# powersupply.net
KiCad netlist of a schematic drawn in EAGLE
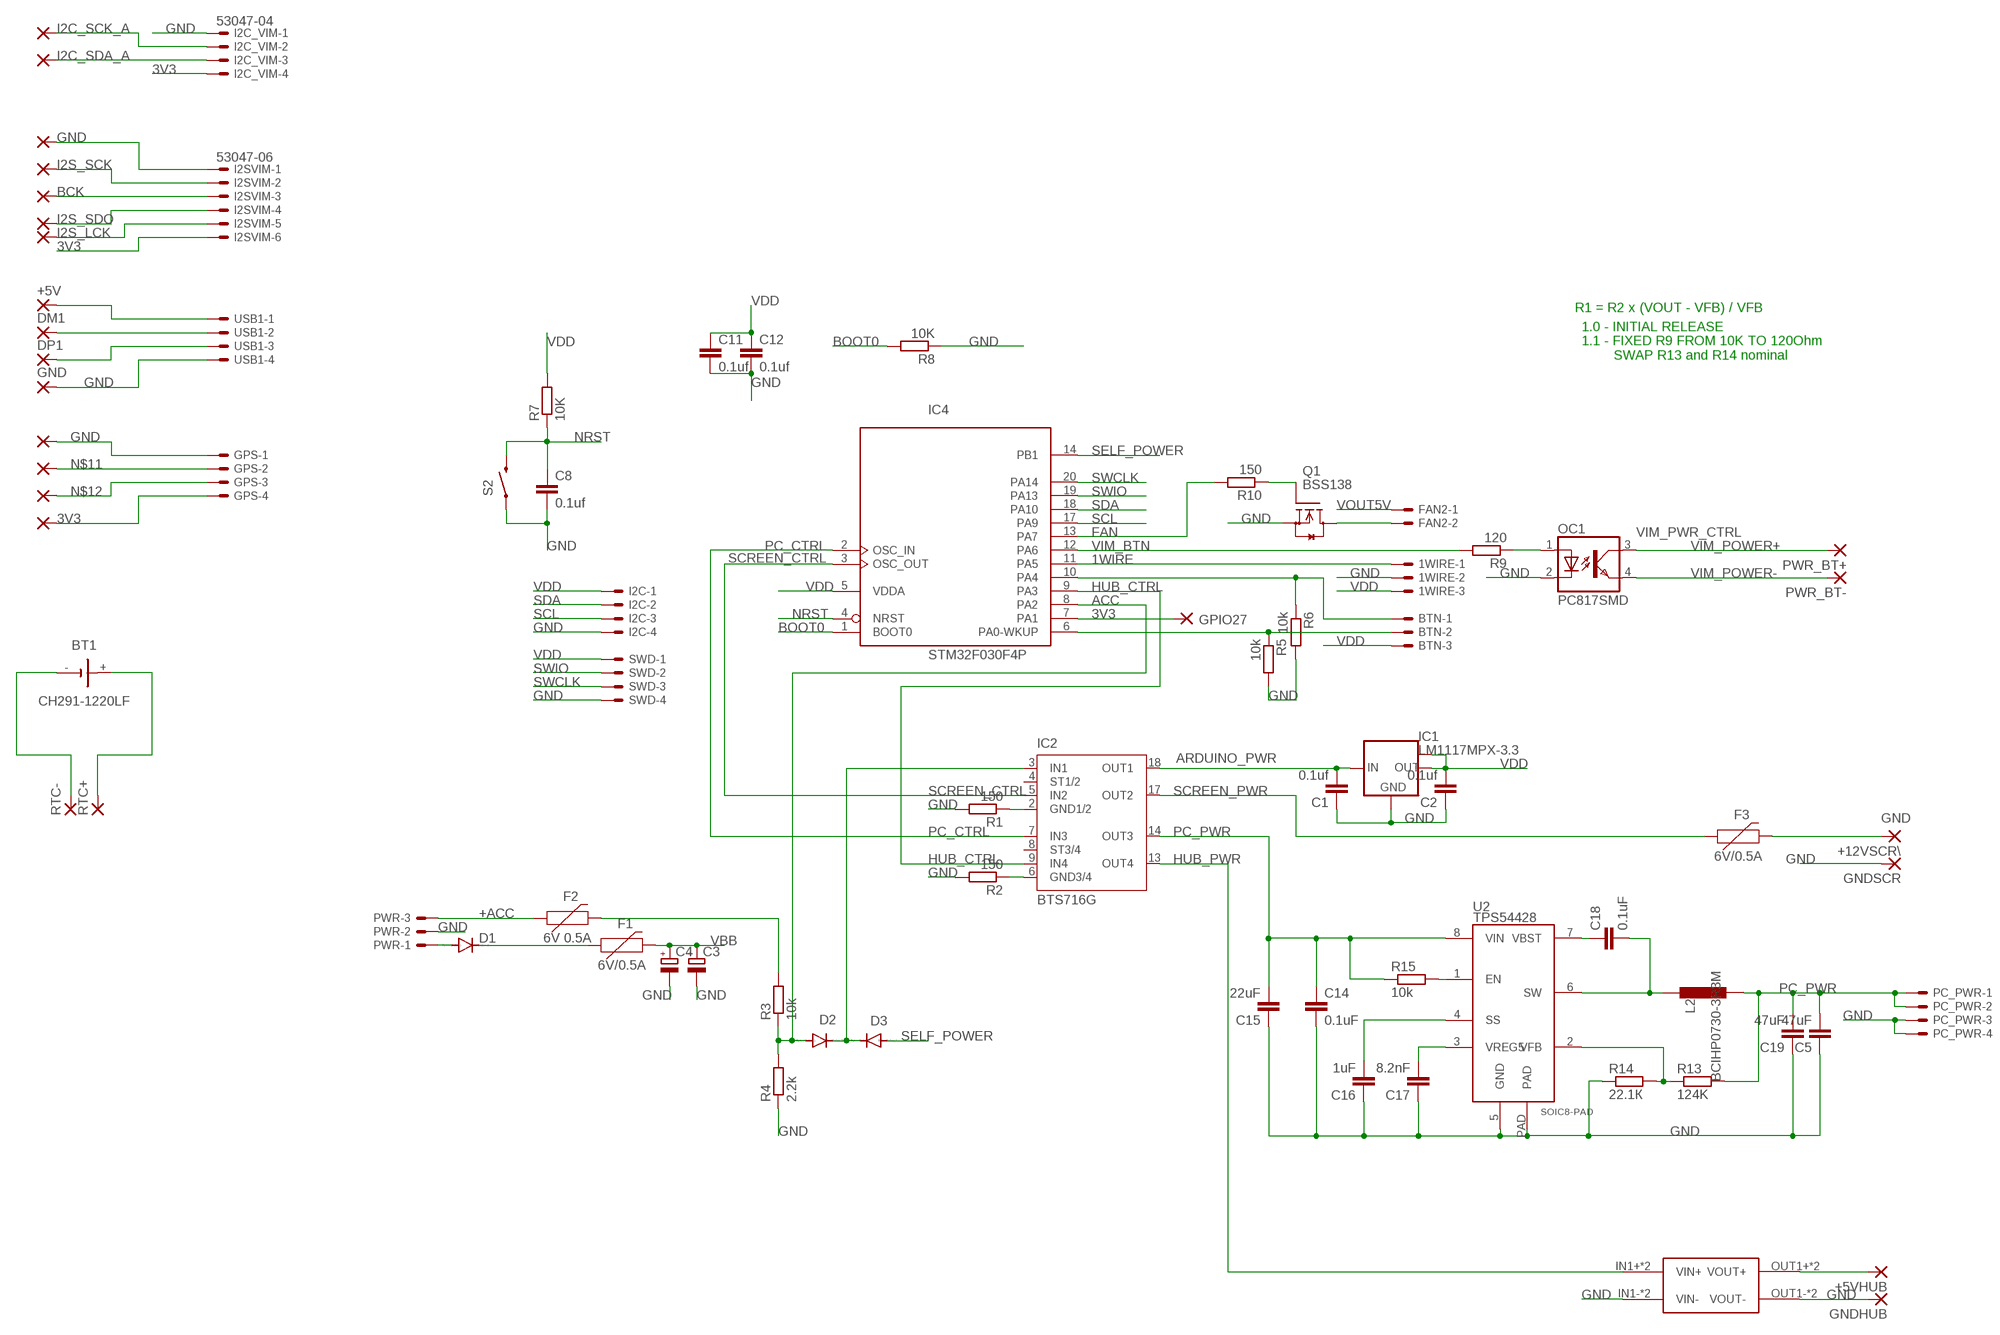
[diagram p0: schematic, sheet 1]

(export (version "E")
  (design (tool "Eeschema 10.0.6"))
  (components
    (comp (ref "+5V")
      (value "1,6/0,8")
      (footprint "eagle-import:1,6_0,8")
      (libsource (lib "eagle-import") (part "1,6/0,8"))
    )
    (comp (ref "+5VHUB")
      (value "1,6/0,8")
      (footprint "eagle-import:1,6_0,8")
      (libsource (lib "eagle-import") (part "1,6/0,8"))
    )
    (comp (ref "+12VSCR\\")
      (value "1,6/0,8")
      (footprint "eagle-import:1,6_0,8")
      (libsource (lib "eagle-import") (part "1,6/0,8"))
    )
    (comp (ref "1WIRE")
      (value "53047-03")
      (footprint "eagle-import:53047-03")
      (fields (field (name "MF") "MOLEX") (field (name "MPN") "530470310"))
      (libsource (lib "eagle-import") (part "53?-03047"))
    )
    (comp (ref "3V3_1")
      (value "1,6/0,8")
      (footprint "eagle-import:1,6_0,8")
      (libsource (lib "eagle-import") (part "1,6/0,8"))
    )
    (comp (ref "22")
      (value "1,6/0,8")
      (footprint "eagle-import:1,6_0,8")
      (libsource (lib "eagle-import") (part "1,6/0,8"))
    )
    (comp (ref "23")
      (value "1,6/0,8")
      (footprint "eagle-import:1,6_0,8")
      (libsource (lib "eagle-import") (part "1,6/0,8"))
    )
    (comp (ref "28")
      (value "1,6/0,8")
      (footprint "eagle-import:1,6_0,8")
      (libsource (lib "eagle-import") (part "1,6/0,8"))
    )
    (comp (ref "29")
      (value "1,6/0,8")
      (footprint "eagle-import:1,6_0,8")
      (libsource (lib "eagle-import") (part "1,6/0,8"))
    )
    (comp (ref "30")
      (value "1,6/0,8")
      (footprint "eagle-import:1,6_0,8")
      (libsource (lib "eagle-import") (part "1,6/0,8"))
    )
    (comp (ref "31")
      (value "1,6/0,8")
      (footprint "eagle-import:1,6_0,8")
      (libsource (lib "eagle-import") (part "1,6/0,8"))
    )
    (comp (ref "32")
      (value "1,6/0,8")
      (footprint "eagle-import:1,6_0,8")
      (libsource (lib "eagle-import") (part "1,6/0,8"))
    )
    (comp (ref "BT1")
      (value "CH291-1220LF")
      (footprint "eagle-import:CH291-1220LF")
      (libsource (lib "eagle-import") (part "CH291-1220LF"))
    )
    (comp (ref "BTN")
      (value "53047-03")
      (footprint "eagle-import:53047-03")
      (fields (field (name "MF") "MOLEX") (field (name "MPN") "530470310"))
      (libsource (lib "eagle-import") (part "53?-03047"))
    )
    (comp (ref "C1")
      (value "0.1uf")
      (footprint "eagle-import:C0805")
      (fields (field (name "MPN") "CL21B104KBFNNNE"))
      (libsource (lib "eagle-import") (part "C-EUC0805"))
    )
    (comp (ref "C2")
      (value "0.1uf")
      (footprint "eagle-import:C0805")
      (fields (field (name "MPN") "CL21B104KBFNNNE"))
      (libsource (lib "eagle-import") (part "C-EUC0805"))
    )
    (comp (ref "C3")
      (value "CPOL-EUUD-8X10")
      (footprint "eagle-import:UD-8X10_NICHICON")
      (libsource (lib "eagle-import") (part "CPOL-EUUD-8X10"))
    )
    (comp (ref "C4")
      (value "CPOL-EUUD-8X10")
      (footprint "eagle-import:UD-8X10_NICHICON")
      (libsource (lib "eagle-import") (part "CPOL-EUUD-8X10"))
    )
    (comp (ref "C5")
      (value "47uF")
      (footprint "eagle-import:C1206")
      (fields (field (name "MPN") "CL31A476MPHNNNE"))
      (libsource (lib "eagle-import") (part "C-EUC1206"))
    )
    (comp (ref "C8")
      (value "0.1uf")
      (footprint "eagle-import:C0805")
      (fields (field (name "MPN") "CL21B104KBFNNNE"))
      (libsource (lib "eagle-import") (part "C-EUC0805"))
    )
    (comp (ref "C11")
      (value "0.1uf")
      (footprint "eagle-import:C0805")
      (fields (field (name "MPN") "CL21B104KBFNNNE"))
      (libsource (lib "eagle-import") (part "C-EUC0805"))
    )
    (comp (ref "C12")
      (value "0.1uf")
      (footprint "eagle-import:C0805")
      (fields (field (name "MPN") "CL21B104KBFNNNE"))
      (libsource (lib "eagle-import") (part "C-EUC0805"))
    )
    (comp (ref "C14")
      (value "0.1uF")
      (footprint "eagle-import:C0805K")
      (fields (field (name "MPN") "CL21B104KBFNNNE"))
      (libsource (lib "eagle-import") (part "C-EUC0805K"))
    )
    (comp (ref "C15")
      (value "22uF")
      (footprint "eagle-import:C0805")
      (fields (field (name "MPN") "CL31A226KAHNNNE"))
      (libsource (lib "eagle-import") (part "C-EUC0805"))
    )
    (comp (ref "C16")
      (value "1uF")
      (footprint "eagle-import:C0805K")
      (fields (field (name "MPN") "CL21B105KAFNNNE"))
      (libsource (lib "eagle-import") (part "C-EUC0805K"))
    )
    (comp (ref "C17")
      (value "8.2nF")
      (footprint "eagle-import:C0805K")
      (fields (field (name "MPN") "CL21B822KBANNNC"))
      (libsource (lib "eagle-import") (part "C-EUC0805K"))
    )
    (comp (ref "C18")
      (value "0.1uF")
      (footprint "eagle-import:C0805K")
      (fields (field (name "MPN") "CL21B104KBFNNNE"))
      (libsource (lib "eagle-import") (part "C-EUC0805K"))
    )
    (comp (ref "C19")
      (value "47uF")
      (footprint "eagle-import:C1206")
      (fields (field (name "MPN") "CL31A476MPHNNNE"))
      (libsource (lib "eagle-import") (part "C-EUC1206"))
    )
    (comp (ref "D1")
      (value "DIODE-SMB")
      (footprint "eagle-import:SMB")
      (libsource (lib "eagle-import") (part "DIODE-SMB"))
    )
    (comp (ref "D2")
      (value "DIODE-SOD323-W")
      (footprint "eagle-import:SOD323-W")
      (libsource (lib "eagle-import") (part "DIODE-SOD323-W"))
    )
    (comp (ref "D3")
      (value "DIODE-SOD323-W")
      (footprint "eagle-import:SOD323-W")
      (libsource (lib "eagle-import") (part "DIODE-SOD323-W"))
    )
    (comp (ref "DM1")
      (value "1,6/0,8")
      (footprint "eagle-import:1,6_0,8")
      (libsource (lib "eagle-import") (part "1,6/0,8"))
    )
    (comp (ref "DP1")
      (value "1,6/0,8")
      (footprint "eagle-import:1,6_0,8")
      (libsource (lib "eagle-import") (part "1,6/0,8"))
    )
    (comp (ref "F1")
      (value "6V/0.5A")
      (footprint "eagle-import:1206")
      (libsource (lib "eagle-import") (part "PPTC_HALF-AMP"))
    )
    (comp (ref "F2")
      (value "6V 0.5A")
      (footprint "eagle-import:0805")
      (libsource (lib "eagle-import") (part "PPTC_6V500MA"))
    )
    (comp (ref "F3")
      (value "6V/0.5A")
      (footprint "eagle-import:1206")
      (libsource (lib "eagle-import") (part "PPTC_HALF-AMP"))
    )
    (comp (ref "FAN2")
      (value "53047-02")
      (footprint "eagle-import:53047-02")
      (fields (field (name "MF") "MOLEX") (field (name "MPN") "53047-0210"))
      (libsource (lib "eagle-import") (part "53?-02047"))
    )
    (comp (ref "GND")
      (value "1,6/0,8")
      (footprint "eagle-import:1,6_0,8")
      (libsource (lib "eagle-import") (part "1,6/0,8"))
    )
    (comp (ref "GNDGPS")
      (value "1,6/0,8")
      (footprint "eagle-import:1,6_0,8")
      (libsource (lib "eagle-import") (part "1,6/0,8"))
    )
    (comp (ref "GNDHUB")
      (value "1,6/0,8")
      (footprint "eagle-import:1,6_0,8")
      (libsource (lib "eagle-import") (part "1,6/0,8"))
    )
    (comp (ref "GNDSCR")
      (value "1,6/0,8")
      (footprint "eagle-import:1,6_0,8")
      (libsource (lib "eagle-import") (part "1,6/0,8"))
    )
    (comp (ref "GPIO27")
      (value "1,6/0,8")
      (footprint "eagle-import:1,6_0,8")
      (libsource (lib "eagle-import") (part "1,6/0,8"))
    )
    (comp (ref "GPS")
      (value "53047-04")
      (footprint "eagle-import:53047-04")
      (fields (field (name "MF") "WALDOM/MOLEX") (field (name "MPN") "53047-0410"))
      (libsource (lib "eagle-import") (part "53?-04047"))
    )
    (comp (ref "I2C")
      (value "i2c")
      (footprint "eagle-import:53047-04")
      (fields (field (name "MF") "WALDOM/MOLEX") (field (name "MPN") "53047-0410"))
      (libsource (lib "eagle-import") (part "53?-04047"))
    )
    (comp (ref "I2C_VIM")
      (value "53047-04")
      (footprint "eagle-import:53047-04")
      (fields (field (name "MF") "WALDOM/MOLEX") (field (name "MPN") "53047-0410"))
      (libsource (lib "eagle-import") (part "53?-04047"))
    )
    (comp (ref "I2SVIM")
      (value "53047-06")
      (footprint "eagle-import:53047-06")
      (libsource (lib "eagle-import") (part "53?-06047"))
    )
    (comp (ref "IC1")
      (value "LM1117MPX-3.3")
      (footprint "eagle-import:SOT223")
      (fields (field (name "MPN") "LM1117IMPX-3.3/NOPB"))
      (libsource (lib "eagle-import") (part "LM1117MPX-3.3"))
    )
    (comp (ref "IC2")
      (value "BTS716G")
      (footprint "eagle-import:PG-DSO-20")
      (libsource (lib "eagle-import") (part "BTS716G"))
    )
    (comp (ref "IC4")
      (value "STM32F030F4P")
      (footprint "eagle-import:TSSOP20-I")
      (libsource (lib "eagle-import") (part "STM32F030FP4"))
    )
    (comp (ref "L2")
      (value "BCIHP0730-3R3M")
      (footprint "eagle-import:VLS4045EX")
      (fields (field (name "MPN") "VLS5045EX-3R3N"))
      (libsource (lib "eagle-import") (part "VLS5045EX"))
    )
    (comp (ref "OC1")
      (value "PC817SMD")
      (footprint "eagle-import:DIL04SMD")
      (fields (field (name "MPN") "PC817X2CSP9F"))
      (libsource (lib "eagle-import") (part "PC817SMD"))
    )
    (comp (ref "PC_PWR")
      (value "i2c")
      (footprint "eagle-import:53047-04")
      (fields (field (name "MF") "WALDOM/MOLEX") (field (name "MPN") "53047-0410"))
      (libsource (lib "eagle-import") (part "53?-04047"))
    )
    (comp (ref "PWR")
      (value "JST-XH-03-PIN-ROUND-PAD")
      (footprint "eagle-import:JST-XH-03-PACKAGE-ROUND-PAD")
      (libsource (lib "eagle-import") (part "JST-XH-03-PIN-ROUND-PAD"))
    )
    (comp (ref "PWR_BT+")
      (value "1,6/0,8")
      (footprint "eagle-import:1,6_0,8")
      (libsource (lib "eagle-import") (part "1,6/0,8"))
    )
    (comp (ref "PWR_BT-")
      (value "1,6/0,8")
      (footprint "eagle-import:1,6_0,8")
      (libsource (lib "eagle-import") (part "1,6/0,8"))
    )
    (comp (ref "Q1")
      (value "BSS138")
      (footprint "eagle-import:SOT23")
      (libsource (lib "eagle-import") (part "BSS138"))
    )
    (comp (ref "R1")
      (value "150")
      (footprint "eagle-import:R0805")
      (libsource (lib "eagle-import") (part "resistor_348_R-EU_R0805"))
    )
    (comp (ref "R2")
      (value "150")
      (footprint "eagle-import:R0805")
      (libsource (lib "eagle-import") (part "resistor_348_R-EU_R0805"))
    )
    (comp (ref "R3")
      (value "10k")
      (footprint "eagle-import:R0805")
      (libsource (lib "eagle-import") (part "resistor_348_R-EU_R0805"))
    )
    (comp (ref "R4")
      (value "2.2k")
      (footprint "eagle-import:R0805")
      (libsource (lib "eagle-import") (part "resistor_348_R-EU_R0805"))
    )
    (comp (ref "R5")
      (value "10k")
      (footprint "eagle-import:R0805")
      (libsource (lib "eagle-import") (part "resistor_348_R-EU_R0805"))
    )
    (comp (ref "R6")
      (value "10k")
      (footprint "eagle-import:R0805")
      (libsource (lib "eagle-import") (part "resistor_348_R-EU_R0805"))
    )
    (comp (ref "R7")
      (value "10K")
      (footprint "eagle-import:M0805")
      (libsource (lib "eagle-import") (part "R-EU_M0805"))
    )
    (comp (ref "R8")
      (value "10K")
      (footprint "eagle-import:M0805")
      (libsource (lib "eagle-import") (part "R-EU_M0805"))
    )
    (comp (ref "R9")
      (value "120")
      (footprint "eagle-import:M0805")
      (libsource (lib "eagle-import") (part "R-EU_M0805"))
    )
    (comp (ref "R10")
      (value "150")
      (footprint "eagle-import:R0805")
      (libsource (lib "eagle-import") (part "resistor_348_R-EU_R0805"))
    )
    (comp (ref "R13")
      (value "124K")
      (footprint "eagle-import:M0805")
      (fields (field (name "MPN") "TR0805B22K1P0525Z"))
      (libsource (lib "eagle-import") (part "R-EU_M0805"))
    )
    (comp (ref "R14")
      (value "22.1К")
      (footprint "eagle-import:M0805")
      (fields (field (name "MPN") "AR05BTCW1253"))
      (libsource (lib "eagle-import") (part "R-EU_M0805"))
    )
    (comp (ref "R15")
      (value "10k")
      (footprint "eagle-import:M0805")
      (libsource (lib "eagle-import") (part "R-EU_M0805"))
    )
    (comp (ref "RTC+")
      (value "1,6/0,8")
      (footprint "eagle-import:1,6_0,8")
      (libsource (lib "eagle-import") (part "1,6/0,8"))
    )
    (comp (ref "RTC-")
      (value "1,6/0,8")
      (footprint "eagle-import:1,6_0,8")
      (libsource (lib "eagle-import") (part "1,6/0,8"))
    )
    (comp (ref "RX")
      (value "1,6/0,8")
      (footprint "eagle-import:1,6_0,8")
      (libsource (lib "eagle-import") (part "1,6/0,8"))
    )
    (comp (ref "S2")
      (value "SWITCH-MOMENTARY-2-SMD-1101NE")
      (footprint "eagle-import:TACTILE-SWITCH-1101NE")
      (libsource (lib "eagle-import") (part "SWITCH-MOMENTARY-2-SMD-1101NE"))
    )
    (comp (ref "SWD")
      (value "53047-04")
      (footprint "eagle-import:53047-04")
      (fields (field (name "MF") "WALDOM/MOLEX") (field (name "MPN") "53047-0410"))
      (libsource (lib "eagle-import") (part "53?-04047"))
    )
    (comp (ref "TX")
      (value "1,6/0,8")
      (footprint "eagle-import:1,6_0,8")
      (libsource (lib "eagle-import") (part "1,6/0,8"))
    )
    (comp (ref "U$1")
      (value "MP1584")
      (footprint "eagle-import:DC-BRICK")
      (libsource (lib "eagle-import") (part "MP1584"))
    )
    (comp (ref "U2")
      (value "TPS54428")
      (footprint "eagle-import:PDSO-8")
      (fields (field (name "PACKAGE") "SOIC8-PAD") (field (name "MPN") "TPS54428DDAR"))
      (libsource (lib "eagle-import") (part "TPS54428"))
    )
    (comp (ref "USB1")
      (value "53047-04")
      (footprint "eagle-import:53047-04")
      (fields (field (name "MF") "WALDOM/MOLEX") (field (name "MPN") "53047-0410"))
      (libsource (lib "eagle-import") (part "53?-04047"))
    )
  )
  (nets
    (net (code "1") (name "/+ACC") (class "Default")
      (node (ref "F2") (pin "2") (pinfunction "2_2") (pintype "bidirectional"))
      (node (ref "R3") (pin "2") (pinfunction "2_2") (pintype "passive"))
    )
    (net (code "2") (name "/1WIRE") (class "Default")
      (node (ref "1WIRE") (pin "1") (pinfunction "S_1") (pintype "passive"))
      (node (ref "IC4") (pin "11") (pinfunction "PA5_11") (pintype "bidirectional"))
    )
    (net (code "3") (name "/3V3") (class "Default")
      (node (ref "3V3_1") (pin "1") (pinfunction "P_1") (pintype "passive"))
      (node (ref "GPIO27") (pin "1") (pinfunction "P_1") (pintype "passive"))
      (node (ref "GPS") (pin "4") (pinfunction "S_4") (pintype "passive"))
      (node (ref "I2C_VIM") (pin "4") (pinfunction "S_4") (pintype "passive"))
      (node (ref "I2SVIM") (pin "6") (pinfunction "S_6") (pintype "passive"))
      (node (ref "IC4") (pin "7") (pinfunction "PA1_7") (pintype "bidirectional"))
    )
    (net (code "4") (name "/ACC") (class "Default")
      (node (ref "D2") (pin "A") (pinfunction "A_A") (pintype "passive"))
      (node (ref "IC4") (pin "8") (pinfunction "PA2_8") (pintype "bidirectional"))
      (node (ref "R3") (pin "1") (pinfunction "1_1") (pintype "passive"))
      (node (ref "R4") (pin "2") (pinfunction "2_2") (pintype "passive"))
    )
    (net (code "5") (name "/ARDUINO_PWR") (class "Default")
      (node (ref "C1") (pin "2") (pinfunction "2_2") (pintype "passive"))
      (node (ref "IC1") (pin "3") (pinfunction "IN_3") (pintype "input"))
      (node (ref "IC2") (pin "18") (pinfunction "OUT1_18") (pintype "output"))
    )
    (net (code "6") (name "/BCK") (class "Default")
      (node (ref "30") (pin "1") (pinfunction "P_1") (pintype "passive"))
      (node (ref "I2SVIM") (pin "3") (pinfunction "S_3") (pintype "passive"))
    )
    (net (code "7") (name "/BOOT0") (class "Default")
      (node (ref "IC4") (pin "1") (pinfunction "BOOT0_1") (pintype "input"))
      (node (ref "R8") (pin "2") (pinfunction "2_2") (pintype "passive"))
    )
    (net (code "8") (name "/FAN") (class "Default")
      (node (ref "IC4") (pin "13") (pinfunction "PA7_13") (pintype "bidirectional"))
      (node (ref "R10") (pin "2") (pinfunction "2_2") (pintype "passive"))
    )
    (net (code "9") (name "/GND") (class "Default")
      (node (ref "1WIRE") (pin "2") (pinfunction "S_2") (pintype "passive"))
      (node (ref "28") (pin "1") (pinfunction "P_1") (pintype "passive"))
      (node (ref "C1") (pin "1") (pinfunction "1_1") (pintype "passive"))
      (node (ref "C11") (pin "2") (pinfunction "2_2") (pintype "passive"))
      (node (ref "C12") (pin "2") (pinfunction "2_2") (pintype "passive"))
      (node (ref "C14") (pin "2") (pinfunction "2_2") (pintype "passive"))
      (node (ref "C15") (pin "1") (pinfunction "1_1") (pintype "passive"))
      (node (ref "C16") (pin "1") (pinfunction "1_1") (pintype "passive"))
      (node (ref "C17") (pin "1") (pinfunction "1_1") (pintype "passive"))
      (node (ref "C19") (pin "1") (pinfunction "1_1") (pintype "passive"))
      (node (ref "C2") (pin "1") (pinfunction "1_1") (pintype "passive"))
      (node (ref "C3") (pin "-") (pinfunction "-_-") (pintype "passive"))
      (node (ref "C4") (pin "-") (pinfunction "-_-") (pintype "passive"))
      (node (ref "C5") (pin "1") (pinfunction "1_1") (pintype "passive"))
      (node (ref "C8") (pin "2") (pinfunction "2_2") (pintype "passive"))
      (node (ref "GND") (pin "1") (pinfunction "P_1") (pintype "passive"))
      (node (ref "GNDGPS") (pin "1") (pinfunction "P_1") (pintype "passive"))
      (node (ref "GNDHUB") (pin "1") (pinfunction "P_1") (pintype "passive"))
      (node (ref "GNDSCR") (pin "1") (pinfunction "P_1") (pintype "passive"))
      (node (ref "GPS") (pin "1") (pinfunction "S_1") (pintype "passive"))
      (node (ref "I2C") (pin "4") (pinfunction "S_4") (pintype "passive"))
      (node (ref "I2C_VIM") (pin "1") (pinfunction "S_1") (pintype "passive"))
      (node (ref "I2SVIM") (pin "1") (pinfunction "S_1") (pintype "passive"))
      (node (ref "IC1") (pin "1") (pinfunction "GND_1") (pintype "input"))
      (node (ref "OC1") (pin "2") (pinfunction "C_2") (pintype "passive"))
      (node (ref "PC_PWR") (pin "3") (pinfunction "S_3") (pintype "passive"))
      (node (ref "PC_PWR") (pin "4") (pinfunction "S_4") (pintype "passive"))
      (node (ref "PWR") (pin "2") (pinfunction "S_2") (pintype "passive"))
      (node (ref "Q1") (pin "2") (pinfunction "S_2") (pintype "passive"))
      (node (ref "R1") (pin "2") (pinfunction "2_2") (pintype "passive"))
      (node (ref "R14") (pin "1") (pinfunction "1_1") (pintype "passive"))
      (node (ref "R2") (pin "2") (pinfunction "2_2") (pintype "passive"))
      (node (ref "R4") (pin "1") (pinfunction "1_1") (pintype "passive"))
      (node (ref "R5") (pin "2") (pinfunction "2_2") (pintype "passive"))
      (node (ref "R6") (pin "2") (pinfunction "2_2") (pintype "passive"))
      (node (ref "R8") (pin "1") (pinfunction "1_1") (pintype "passive"))
      (node (ref "S2") (pin "P$1") (pinfunction "1_P$1") (pintype "passive"))
      (node (ref "SWD") (pin "4") (pinfunction "S_4") (pintype "passive"))
      (node (ref "U$1") (pin "IN1-") (pinfunction "VIN-_IN1-") (pintype "input"))
      (node (ref "U$1") (pin "IN2-") (pinfunction "VIN-_IN2-") (pintype "input"))
      (node (ref "U$1") (pin "OUT1-") (pinfunction "VOUT-_OUT1-") (pintype "output"))
      (node (ref "U$1") (pin "OUT2-") (pinfunction "VOUT-_OUT2-") (pintype "output"))
      (node (ref "U2") (pin "5") (pinfunction "GND_5") (pintype "bidirectional"))
      (node (ref "U2") (pin "PAD") (pinfunction "PAD_PAD") (pintype "bidirectional"))
      (node (ref "USB1") (pin "4") (pinfunction "S_4") (pintype "passive"))
    )
    (net (code "10") (name "/HUB_CTRL") (class "Default")
      (node (ref "IC2") (pin "9") (pinfunction "IN4_9") (pintype "input"))
      (node (ref "IC4") (pin "9") (pinfunction "PA3_9") (pintype "bidirectional"))
    )
    (net (code "11") (name "/HUB_PWR") (class "Default")
      (node (ref "IC2") (pin "13") (pinfunction "OUT4_13") (pintype "output"))
      (node (ref "U$1") (pin "IN1+") (pinfunction "VIN+_IN1+") (pintype "input"))
      (node (ref "U$1") (pin "IN2+") (pinfunction "VIN+_IN2+") (pintype "input"))
    )
    (net (code "12") (name "/I2C_SCK_A") (class "Default")
      (node (ref "22") (pin "1") (pinfunction "P_1") (pintype "passive"))
      (node (ref "I2C_VIM") (pin "2") (pinfunction "S_2") (pintype "passive"))
    )
    (net (code "13") (name "/I2C_SDA_A") (class "Default")
      (node (ref "23") (pin "1") (pinfunction "P_1") (pintype "passive"))
      (node (ref "I2C_VIM") (pin "3") (pinfunction "S_3") (pintype "passive"))
    )
    (net (code "14") (name "/I2S_LCK") (class "Default")
      (node (ref "32") (pin "1") (pinfunction "P_1") (pintype "passive"))
      (node (ref "I2SVIM") (pin "5") (pinfunction "S_5") (pintype "passive"))
    )
    (net (code "15") (name "/I2S_SCK") (class "Default")
      (node (ref "29") (pin "1") (pinfunction "P_1") (pintype "passive"))
      (node (ref "I2SVIM") (pin "2") (pinfunction "S_2") (pintype "passive"))
    )
    (net (code "16") (name "/I2S_SDO") (class "Default")
      (node (ref "31") (pin "1") (pinfunction "P_1") (pintype "passive"))
      (node (ref "I2SVIM") (pin "4") (pinfunction "S_4") (pintype "passive"))
    )
    (net (code "17") (name "/N$11") (class "Default")
      (node (ref "GPS") (pin "2") (pinfunction "S_2") (pintype "passive"))
      (node (ref "RX") (pin "1") (pinfunction "P_1") (pintype "passive"))
    )
    (net (code "18") (name "/N$12") (class "Default")
      (node (ref "GPS") (pin "3") (pinfunction "S_3") (pintype "passive"))
      (node (ref "TX") (pin "1") (pinfunction "P_1") (pintype "passive"))
    )
    (net (code "19") (name "/NRST") (class "Default")
      (node (ref "C8") (pin "1") (pinfunction "1_1") (pintype "passive"))
      (node (ref "IC4") (pin "4") (pinfunction "NRST_4") (pintype "bidirectional"))
      (node (ref "R7") (pin "1") (pinfunction "1_1") (pintype "passive"))
      (node (ref "S2") (pin "P$2") (pinfunction "2_P$2") (pintype "passive"))
    )
    (net (code "20") (name "/PC_CTRL") (class "Default")
      (node (ref "IC2") (pin "7") (pinfunction "IN3_7") (pintype "input"))
      (node (ref "IC4") (pin "2") (pinfunction "OSC_IN_2") (pintype "bidirectional"))
    )
    (net (code "21") (name "/PC_PWR") (class "Default")
      (node (ref "C14") (pin "1") (pinfunction "1_1") (pintype "passive"))
      (node (ref "C15") (pin "2") (pinfunction "2_2") (pintype "passive"))
      (node (ref "IC2") (pin "14") (pinfunction "OUT3_14") (pintype "output"))
      (node (ref "R15") (pin "1") (pinfunction "1_1") (pintype "passive"))
      (node (ref "U2") (pin "8") (pinfunction "VIN_8") (pintype "bidirectional"))
    )
    (net (code "22") (name "/SCL") (class "Default")
      (node (ref "I2C") (pin "3") (pinfunction "S_3") (pintype "passive"))
      (node (ref "IC4") (pin "17") (pinfunction "PA9_17") (pintype "bidirectional"))
    )
    (net (code "23") (name "/SCREEN_CTRL") (class "Default")
      (node (ref "IC2") (pin "5") (pinfunction "IN2_5") (pintype "input"))
      (node (ref "IC4") (pin "3") (pinfunction "OSC_OUT_3") (pintype "bidirectional"))
    )
    (net (code "24") (name "/SCREEN_PWR") (class "Default")
      (node (ref "F3") (pin "1") (pinfunction "1_1") (pintype "bidirectional"))
      (node (ref "IC2") (pin "17") (pinfunction "OUT2_17") (pintype "output"))
    )
    (net (code "25") (name "/SDA") (class "Default")
      (node (ref "I2C") (pin "2") (pinfunction "S_2") (pintype "passive"))
      (node (ref "IC4") (pin "18") (pinfunction "PA10_18") (pintype "bidirectional"))
    )
    (net (code "26") (name "/SELF_POWER") (class "Default")
      (node (ref "D3") (pin "A") (pinfunction "A_A") (pintype "passive"))
      (node (ref "IC4") (pin "14") (pinfunction "PB1_14") (pintype "bidirectional"))
    )
    (net (code "27") (name "/SWCLK") (class "Default")
      (node (ref "IC4") (pin "20") (pinfunction "PA14_20") (pintype "bidirectional"))
      (node (ref "SWD") (pin "3") (pinfunction "S_3") (pintype "passive"))
    )
    (net (code "28") (name "/SWIO") (class "Default")
      (node (ref "IC4") (pin "19") (pinfunction "PA13_19") (pintype "bidirectional"))
      (node (ref "SWD") (pin "2") (pinfunction "S_2") (pintype "passive"))
    )
    (net (code "29") (name "/VBB") (class "Default")
      (node (ref "C3") (pin "+") (pinfunction "+_+") (pintype "passive"))
      (node (ref "C4") (pin "+") (pinfunction "+_+") (pintype "passive"))
      (node (ref "F1") (pin "2") (pinfunction "2_2") (pintype "bidirectional"))
    )
    (net (code "30") (name "/VDD") (class "Default")
      (node (ref "1WIRE") (pin "3") (pinfunction "S_3") (pintype "passive"))
      (node (ref "BTN") (pin "3") (pinfunction "S_3") (pintype "passive"))
      (node (ref "C11") (pin "1") (pinfunction "1_1") (pintype "passive"))
      (node (ref "C12") (pin "1") (pinfunction "1_1") (pintype "passive"))
      (node (ref "C2") (pin "2") (pinfunction "2_2") (pintype "passive"))
      (node (ref "I2C") (pin "1") (pinfunction "S_1") (pintype "passive"))
      (node (ref "IC1") (pin "2") (pinfunction "OUT_2") (pintype "passive"))
      (node (ref "IC1") (pin "TAB") (pinfunction "OUT1_TAB") (pintype "passive"))
      (node (ref "IC4") (pin "5") (pinfunction "VDDA_5") (pintype "power_in"))
      (node (ref "R7") (pin "2") (pinfunction "2_2") (pintype "passive"))
      (node (ref "SWD") (pin "1") (pinfunction "S_1") (pintype "passive"))
    )
    (net (code "31") (name "/VIM_BTN") (class "Default")
      (node (ref "IC4") (pin "12") (pinfunction "PA6_12") (pintype "bidirectional"))
      (node (ref "R9") (pin "2") (pinfunction "2_2") (pintype "passive"))
    )
    (net (code "32") (name "/VIM_POWER+") (class "Default")
      (node (ref "OC1") (pin "3") (pinfunction "COL_3") (pintype "passive"))
      (node (ref "PWR_BT+") (pin "1") (pinfunction "P_1") (pintype "passive"))
    )
    (net (code "33") (name "/VIM_POWER-") (class "Default")
      (node (ref "OC1") (pin "4") (pinfunction "EMIT_4") (pintype "passive"))
      (node (ref "PWR_BT-") (pin "1") (pinfunction "P_1") (pintype "passive"))
    )
    (net (code "34") (name "/VIM_PWR_CTRL") (class "Default")
      (node (ref "OC1") (pin "1") (pinfunction "A_1") (pintype "passive"))
      (node (ref "R9") (pin "1") (pinfunction "1_1") (pintype "passive"))
    )
    (net (code "35") (name "/VOUT5V") (class "Default")
      (node (ref "C19") (pin "2") (pinfunction "2_2") (pintype "passive"))
      (node (ref "C5") (pin "2") (pinfunction "2_2") (pintype "passive"))
      (node (ref "FAN2") (pin "1") (pinfunction "S_1") (pintype "passive"))
      (node (ref "L2") (pin "2") (pinfunction "2_2") (pintype "passive"))
      (node (ref "PC_PWR") (pin "1") (pinfunction "S_1") (pintype "passive"))
      (node (ref "PC_PWR") (pin "2") (pinfunction "S_2") (pintype "passive"))
      (node (ref "R13") (pin "2") (pinfunction "2_2") (pintype "passive"))
    )
    (net (code "36") (name "Net-(+5V-P)") (class "Default")
      (node (ref "+5V") (pin "1") (pinfunction "P_1") (pintype "passive"))
      (node (ref "USB1") (pin "1") (pinfunction "S_1") (pintype "passive"))
    )
    (net (code "37") (name "Net-(+5VHUB-P)") (class "Default")
      (node (ref "+5VHUB") (pin "1") (pinfunction "P_1") (pintype "passive"))
      (node (ref "U$1") (pin "OUT1+") (pinfunction "VOUT+_OUT1+") (pintype "output"))
      (node (ref "U$1") (pin "OUT2+") (pinfunction "VOUT+_OUT2+") (pintype "output"))
    )
    (net (code "38") (name "Net-(+12VSCR\\-P)") (class "Default")
      (node (ref "+12VSCR\\") (pin "1") (pinfunction "P_1") (pintype "passive"))
      (node (ref "F3") (pin "2") (pinfunction "2_2") (pintype "bidirectional"))
    )
    (net (code "39") (name "Net-(BTNA-S)") (class "Default")
      (node (ref "BTN") (pin "1") (pinfunction "S_1") (pintype "passive"))
      (node (ref "IC4") (pin "10") (pinfunction "PA4_10") (pintype "bidirectional"))
      (node (ref "R6") (pin "1") (pinfunction "1_1") (pintype "passive"))
    )
    (net (code "40") (name "Net-(BTNB-S)") (class "Default")
      (node (ref "BTN") (pin "2") (pinfunction "S_2") (pintype "passive"))
      (node (ref "IC4") (pin "6") (pinfunction "PA0-WKUP_6") (pintype "bidirectional"))
      (node (ref "R5") (pin "1") (pinfunction "1_1") (pintype "passive"))
    )
    (net (code "41") (name "Net-(D1-PadC)") (class "Default")
      (node (ref "D1") (pin "C") (pinfunction "C_C") (pintype "passive"))
      (node (ref "F1") (pin "1") (pinfunction "1_1") (pintype "bidirectional"))
    )
    (net (code "42") (name "Net-(DM1-P)") (class "Default")
      (node (ref "DM1") (pin "1") (pinfunction "P_1") (pintype "passive"))
      (node (ref "USB1") (pin "2") (pinfunction "S_2") (pintype "passive"))
    )
    (net (code "43") (name "Net-(DP1-P)") (class "Default")
      (node (ref "DP1") (pin "1") (pinfunction "P_1") (pintype "passive"))
      (node (ref "USB1") (pin "3") (pinfunction "S_3") (pintype "passive"))
    )
    (net (code "44") (name "Net-(FAN2B-S)") (class "Default")
      (node (ref "FAN2") (pin "2") (pinfunction "S_2") (pintype "passive"))
      (node (ref "Q1") (pin "3") (pinfunction "D_3") (pintype "passive"))
    )
    (net (code "45") (name "Net-(IC2A-GND1{slash}2)") (class "Default")
      (node (ref "IC2") (pin "2") (pinfunction "GND1/2_2") (pintype "input"))
      (node (ref "R1") (pin "1") (pinfunction "1_1") (pintype "passive"))
    )
    (net (code "46") (name "Net-(IC2A-GND3{slash}4)") (class "Default")
      (node (ref "IC2") (pin "6") (pinfunction "GND3/4_6") (pintype "input"))
      (node (ref "R2") (pin "1") (pinfunction "1_1") (pintype "passive"))
    )
    (net (code "47") (name "Net-(IC2A-IN1)") (class "Default")
      (node (ref "D2") (pin "C") (pinfunction "C_C") (pintype "passive"))
      (node (ref "D3") (pin "C") (pinfunction "C_C") (pintype "passive"))
      (node (ref "IC2") (pin "3") (pinfunction "IN1_3") (pintype "input"))
    )
    (net (code "48") (name "Net-(PWRA-S)") (class "Default")
      (node (ref "D1") (pin "A") (pinfunction "A_A") (pintype "passive"))
      (node (ref "PWR") (pin "1") (pinfunction "S_1") (pintype "passive"))
    )
    (net (code "49") (name "Net-(PWRC-S)") (class "Default")
      (node (ref "F2") (pin "1") (pinfunction "1_1") (pintype "bidirectional"))
      (node (ref "PWR") (pin "3") (pinfunction "S_3") (pintype "passive"))
    )
    (net (code "50") (name "Net-(Q1-G)") (class "Default")
      (node (ref "Q1") (pin "1") (pinfunction "G_1") (pintype "passive"))
      (node (ref "R10") (pin "1") (pinfunction "1_1") (pintype "passive"))
    )
    (net (code "51") (name "Net-(RTC+-P)") (class "Default")
      (node (ref "BT1") (pin "+") (pinfunction "+_+") (pintype "passive"))
      (node (ref "RTC+") (pin "1") (pinfunction "P_1") (pintype "passive"))
    )
    (net (code "52") (name "Net-(RTC--P)") (class "Default")
      (node (ref "BT1") (pin "-") (pinfunction "-_-") (pintype "passive"))
      (node (ref "RTC-") (pin "1") (pinfunction "P_1") (pintype "passive"))
    )
    (net (code "53") (name "Net-(U2-EN)") (class "Default")
      (node (ref "R15") (pin "2") (pinfunction "2_2") (pintype "passive"))
      (node (ref "U2") (pin "1") (pinfunction "EN_1") (pintype "bidirectional"))
    )
    (net (code "54") (name "Net-(U2-SS)") (class "Default")
      (node (ref "C16") (pin "2") (pinfunction "2_2") (pintype "passive"))
      (node (ref "U2") (pin "4") (pinfunction "SS_4") (pintype "bidirectional"))
    )
    (net (code "55") (name "Net-(U2-SW)") (class "Default")
      (node (ref "C18") (pin "2") (pinfunction "2_2") (pintype "passive"))
      (node (ref "L2") (pin "1") (pinfunction "1_1") (pintype "passive"))
      (node (ref "U2") (pin "6") (pinfunction "SW_6") (pintype "bidirectional"))
    )
    (net (code "56") (name "Net-(U2-VBST)") (class "Default")
      (node (ref "C18") (pin "1") (pinfunction "1_1") (pintype "passive"))
      (node (ref "U2") (pin "7") (pinfunction "VBST_7") (pintype "bidirectional"))
    )
    (net (code "57") (name "Net-(U2-VFB)") (class "Default")
      (node (ref "R13") (pin "1") (pinfunction "1_1") (pintype "passive"))
      (node (ref "R14") (pin "2") (pinfunction "2_2") (pintype "passive"))
      (node (ref "U2") (pin "2") (pinfunction "VFB_2") (pintype "bidirectional"))
    )
    (net (code "58") (name "Net-(U2-VREG5)") (class "Default")
      (node (ref "C17") (pin "2") (pinfunction "2_2") (pintype "passive"))
      (node (ref "U2") (pin "3") (pinfunction "VREG5_3") (pintype "bidirectional"))
    )
    (net (code "59") (name "unconnected-(IC2A-ST1{slash}2-Pad4)") (class "Default")
      (node (ref "IC2") (pin "4") (pinfunction "ST1/2_4") (pintype "input"))
    )
    (net (code "60") (name "unconnected-(IC2A-ST3{slash}4-Pad8)") (class "Default")
      (node (ref "IC2") (pin "8") (pinfunction "ST3/4_8") (pintype "input"))
    )
  )
)
